# v1.net
KiCad netlist of a schematic drawn in Altium Designer
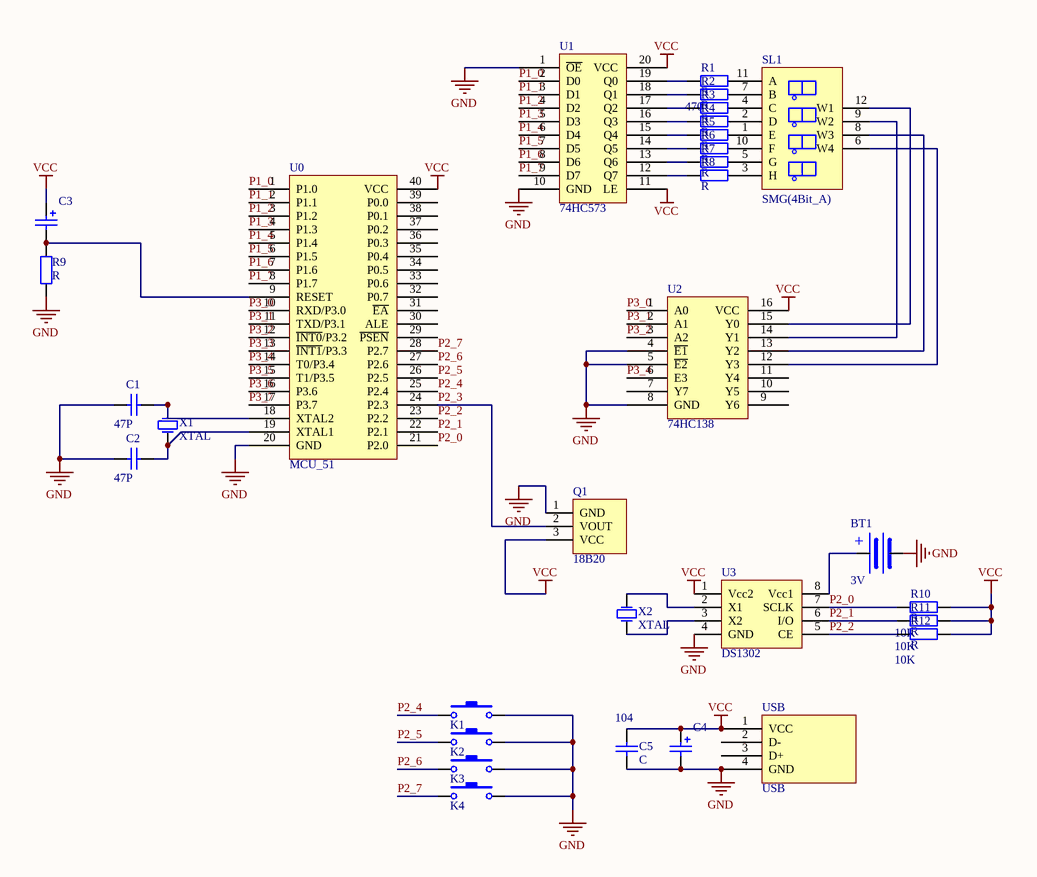
[diagram p0: 电子钟v1.SchDoc]

(export (version "E")
  (design (tool "Eeschema 10.0.6"))
  (components
    (comp (ref "BT1") (value "3V") (footprint "DCH_22") (libsource (lib "我的库") (part "BATTER")))
    (comp (ref "C1")
      (value "47pf")
      (footprint "瓷片电容")
      (fields (field (name "SIZE") "47P"))
      (libsource (lib "我的库") (part "C"))
    )
    (comp (ref "C2")
      (value "C")
      (footprint "瓷片电容")
      (fields (field (name "SIZE") "47P"))
      (libsource (lib "我的库") (part "C"))
    )
    (comp (ref "C3") (value "CD") (footprint "电解电容（小型）") (libsource (lib "我的库") (part "CD")))
    (comp (ref "C4") (value "CD") (footprint "电解电容（小型）") (libsource (lib "我的库") (part "CD")))
    (comp (ref "C5")
      (value "C")
      (footprint "瓷片电容")
      (fields (field (name "SIZE") "104"))
      (libsource (lib "我的库") (part "C"))
    )
    (comp (ref "K1")
      (value "switch-anniu")
      (footprint "6*6按钮开关")
      (libsource (lib "我的库") (part "switch-anniu"))
    )
    (comp (ref "K2")
      (value "switch-anniu")
      (footprint "6*6按钮开关")
      (libsource (lib "我的库") (part "switch-anniu"))
    )
    (comp (ref "K3")
      (value "switch-anniu")
      (footprint "6*6按钮开关")
      (libsource (lib "我的库") (part "switch-anniu"))
    )
    (comp (ref "K4")
      (value "switch-anniu")
      (footprint "6*6按钮开关")
      (libsource (lib "我的库") (part "switch-anniu"))
    )
    (comp (ref "Q1") (value "18B20") (footprint "三极管（小体3个脚）") (libsource (lib "我的库") (part "18B20")))
    (comp (ref "R1")
      (value "R")
      (footprint "电阻-0.25W")
      (fields (field (name "SIZE") "470"))
      (libsource (lib "我的库") (part "R"))
    )
    (comp (ref "R2") (value "R") (footprint "电阻-0.25W") (libsource (lib "我的库") (part "R")))
    (comp (ref "R3") (value "R") (footprint "电阻-0.25W") (libsource (lib "我的库") (part "R")))
    (comp (ref "R4") (value "R") (footprint "电阻-0.25W") (libsource (lib "我的库") (part "R")))
    (comp (ref "R5") (value "R") (footprint "电阻-0.25W") (libsource (lib "我的库") (part "R")))
    (comp (ref "R6") (value "R") (footprint "电阻-0.25W") (libsource (lib "我的库") (part "R")))
    (comp (ref "R7") (value "R") (footprint "电阻-0.25W") (libsource (lib "我的库") (part "R")))
    (comp (ref "R8") (value "R") (footprint "电阻-0.25W") (libsource (lib "我的库") (part "R")))
    (comp (ref "R9") (value "R") (footprint "电阻-0.25W") (libsource (lib "") (part "R_1")))
    (comp (ref "R10")
      (value "R")
      (footprint "电阻-0.25W")
      (fields (field (name "SIZE") "10K"))
      (libsource (lib "我的库") (part "R"))
    )
    (comp (ref "R11")
      (value "R")
      (footprint "电阻-0.25W")
      (fields (field (name "SIZE") "10K"))
      (libsource (lib "我的库") (part "R"))
    )
    (comp (ref "R12")
      (value "R")
      (footprint "电阻-0.25W")
      (fields (field (name "SIZE") "10K"))
      (libsource (lib "我的库") (part "R"))
    )
    (comp (ref "SL1")
      (value "SMG(4Bit_A)")
      (footprint "4位数码管（19*50mm）")
      (libsource (lib "我的库") (part "SMG(4Bit_A)"))
    )
    (comp (ref "U0") (value "MCU_51") (footprint "DIP-40") (libsource (lib "我的库") (part "MCU_51")))
    (comp (ref "U1") (value "74HC573") (footprint "DIP20插座") (libsource (lib "mylib") (part "74HC573")))
    (comp (ref "U2") (value "74HC138") (footprint "DIP16插座") (libsource (lib "mylib") (part "74HC138")))
    (comp (ref "U3") (value "DS1302") (footprint "DIP-8") (libsource (lib "我的库") (part "DS1302")))
    (comp (ref "USB") (value "USB") (footprint "USB阴头") (libsource (lib "GBY的原理图库") (part "USB")))
    (comp (ref "X1") (value "XTAL") (footprint "无源晶体（2个脚）") (libsource (lib "我的库") (part "XTAL")))
    (comp (ref "X2") (value "XTAL") (footprint "无源晶体（小）") (libsource (lib "我的库") (part "XTAL")))
  )
  (nets
    (net (code "1") (name "/P1_0") (class "Default")
      (node (ref "U0") (pin "1") (pinfunction "P1.0_1") (pintype "passive"))
      (node (ref "U1") (pin "2") (pinfunction "D0_2") (pintype "passive"))
    )
    (net (code "2") (name "/P1_1") (class "Default")
      (node (ref "U0") (pin "2") (pinfunction "P1.1_2") (pintype "passive"))
      (node (ref "U1") (pin "3") (pinfunction "D1_3") (pintype "passive"))
    )
    (net (code "3") (name "/P1_2") (class "Default")
      (node (ref "U0") (pin "3") (pinfunction "P1.2_3") (pintype "passive"))
      (node (ref "U1") (pin "4") (pinfunction "D2_4") (pintype "passive"))
    )
    (net (code "4") (name "/P1_3") (class "Default")
      (node (ref "U0") (pin "4") (pinfunction "P1.3_4") (pintype "passive"))
      (node (ref "U1") (pin "5") (pinfunction "D3_5") (pintype "passive"))
    )
    (net (code "5") (name "/P1_4") (class "Default")
      (node (ref "U0") (pin "5") (pinfunction "P1.4_5") (pintype "passive"))
      (node (ref "U1") (pin "6") (pinfunction "D4_6") (pintype "passive"))
    )
    (net (code "6") (name "/P1_5") (class "Default")
      (node (ref "U0") (pin "6") (pinfunction "P1.5_6") (pintype "passive"))
      (node (ref "U1") (pin "7") (pinfunction "D5_7") (pintype "passive"))
    )
    (net (code "7") (name "/P1_6") (class "Default")
      (node (ref "U0") (pin "7") (pinfunction "P1.6_7") (pintype "passive"))
      (node (ref "U1") (pin "8") (pinfunction "D6_8") (pintype "passive"))
    )
    (net (code "8") (name "/P1_7") (class "Default")
      (node (ref "U0") (pin "8") (pinfunction "P1.7_8") (pintype "passive"))
      (node (ref "U1") (pin "9") (pinfunction "D7_9") (pintype "passive"))
    )
    (net (code "9") (name "/P2_0") (class "Default")
      (node (ref "R10") (pin "1") (pinfunction "1_1") (pintype "passive"))
      (node (ref "U0") (pin "21") (pinfunction "P2.0_21") (pintype "passive"))
      (node (ref "U3") (pin "7") (pinfunction "SCLK_7") (pintype "passive"))
    )
    (net (code "10") (name "/P2_1") (class "Default")
      (node (ref "R11") (pin "1") (pinfunction "1_1") (pintype "passive"))
      (node (ref "U0") (pin "22") (pinfunction "P2.1_22") (pintype "passive"))
      (node (ref "U3") (pin "6") (pinfunction "I/O_6") (pintype "passive"))
    )
    (net (code "11") (name "/P2_2") (class "Default")
      (node (ref "R12") (pin "1") (pinfunction "1_1") (pintype "passive"))
      (node (ref "U0") (pin "23") (pinfunction "P2.2_23") (pintype "passive"))
      (node (ref "U3") (pin "5") (pinfunction "CE_5") (pintype "passive"))
    )
    (net (code "12") (name "/P2_3") (class "Default")
      (node (ref "Q1") (pin "2") (pinfunction "VOUT_2") (pintype "passive"))
      (node (ref "U0") (pin "24") (pinfunction "P2.3_24") (pintype "passive"))
    )
    (net (code "13") (name "/P2_4") (class "Default")
      (node (ref "K1") (pin "1") (pinfunction "1_1") (pintype "passive"))
      (node (ref "U0") (pin "25") (pinfunction "P2.4_25") (pintype "passive"))
    )
    (net (code "14") (name "/P2_5") (class "Default")
      (node (ref "K2") (pin "1") (pinfunction "1_1") (pintype "passive"))
      (node (ref "U0") (pin "26") (pinfunction "P2.5_26") (pintype "passive"))
    )
    (net (code "15") (name "/P2_6") (class "Default")
      (node (ref "K3") (pin "1") (pinfunction "1_1") (pintype "passive"))
      (node (ref "U0") (pin "27") (pinfunction "P2.6_27") (pintype "passive"))
    )
    (net (code "16") (name "/P2_7") (class "Default")
      (node (ref "K4") (pin "1") (pinfunction "1_1") (pintype "passive"))
      (node (ref "U0") (pin "28") (pinfunction "P2.7_28") (pintype "passive"))
    )
    (net (code "17") (name "/P3_0") (class "Default")
      (node (ref "U0") (pin "10") (pinfunction "RXD/P3.0_10") (pintype "passive"))
      (node (ref "U2") (pin "1") (pinfunction "A0_1") (pintype "passive"))
    )
    (net (code "18") (name "/P3_1") (class "Default")
      (node (ref "U0") (pin "11") (pinfunction "TXD/P3.1_11") (pintype "passive"))
      (node (ref "U2") (pin "2") (pinfunction "A1_2") (pintype "passive"))
    )
    (net (code "19") (name "/P3_2") (class "Default")
      (node (ref "U0") (pin "12") (pinfunction "~{INT0}/P3.2_12") (pintype "passive"))
      (node (ref "U2") (pin "3") (pinfunction "A2_3") (pintype "passive"))
    )
    (net (code "20") (name "/P3_3") (class "Default")
      (node (ref "U0") (pin "13") (pinfunction "~{INT1}/P3.3_13") (pintype "passive"))
    )
    (net (code "21") (name "/P3_4") (class "Default")
      (node (ref "U0") (pin "14") (pinfunction "T0/P3.4_14") (pintype "passive"))
      (node (ref "U2") (pin "6") (pinfunction "E3_6") (pintype "passive"))
    )
    (net (code "22") (name "/P3_5") (class "Default")
      (node (ref "U0") (pin "15") (pinfunction "T1/P3.5_15") (pintype "passive"))
    )
    (net (code "23") (name "/P3_6") (class "Default")
      (node (ref "U0") (pin "16") (pinfunction "P3.6_16") (pintype "passive"))
    )
    (net (code "24") (name "/P3_7") (class "Default")
      (node (ref "U0") (pin "17") (pinfunction "P3.7_17") (pintype "passive"))
    )
    (net (code "25") (name "GND") (class "Default")
      (node (ref "BT1") (pin "2") (pinfunction "GND_2") (pintype "passive"))
      (node (ref "C1") (pin "1") (pinfunction "1_1") (pintype "passive"))
      (node (ref "C2") (pin "1") (pinfunction "1_1") (pintype "passive"))
      (node (ref "C4") (pin "2") (pinfunction "2_2") (pintype "passive"))
      (node (ref "C5") (pin "1") (pinfunction "1_1") (pintype "passive"))
      (node (ref "K1") (pin "2") (pinfunction "2_2") (pintype "passive"))
      (node (ref "K2") (pin "2") (pinfunction "2_2") (pintype "passive"))
      (node (ref "K3") (pin "2") (pinfunction "2_2") (pintype "passive"))
      (node (ref "K4") (pin "2") (pinfunction "2_2") (pintype "passive"))
      (node (ref "Q1") (pin "1") (pinfunction "GND_1") (pintype "passive"))
      (node (ref "R9") (pin "1") (pinfunction "1_1") (pintype "passive"))
      (node (ref "U0") (pin "20") (pinfunction "GND_20") (pintype "passive"))
      (node (ref "U1") (pin "1") (pinfunction "~{OE}_1") (pintype "passive"))
      (node (ref "U1") (pin "10") (pinfunction "GND_10") (pintype "passive"))
      (node (ref "U2") (pin "4") (pinfunction "~{E1}_4") (pintype "passive"))
      (node (ref "U2") (pin "5") (pinfunction "~{E2}_5") (pintype "passive"))
      (node (ref "U2") (pin "8") (pinfunction "GND_8") (pintype "power_in"))
      (node (ref "U3") (pin "4") (pinfunction "GND_4") (pintype "passive"))
      (node (ref "USB") (pin "4") (pinfunction "GND_4") (pintype "passive"))
    )
    (net (code "26") (name "Net-(BT1-VCC)") (class "Default")
      (node (ref "BT1") (pin "1") (pinfunction "VCC_1") (pintype "passive"))
      (node (ref "U3") (pin "8") (pinfunction "Vcc1_8") (pintype "passive"))
    )
    (net (code "27") (name "Net-(SL1-A)") (class "Default")
      (node (ref "R1") (pin "2") (pinfunction "2_2") (pintype "passive"))
      (node (ref "SL1") (pin "11") (pinfunction "A_11") (pintype "passive"))
    )
    (net (code "28") (name "Net-(SL1-B)") (class "Default")
      (node (ref "R2") (pin "2") (pinfunction "2_2") (pintype "passive"))
      (node (ref "SL1") (pin "7") (pinfunction "B_7") (pintype "passive"))
    )
    (net (code "29") (name "Net-(SL1-C)") (class "Default")
      (node (ref "R3") (pin "2") (pinfunction "2_2") (pintype "passive"))
      (node (ref "SL1") (pin "4") (pinfunction "C_4") (pintype "passive"))
    )
    (net (code "30") (name "Net-(SL1-D)") (class "Default")
      (node (ref "R4") (pin "2") (pinfunction "2_2") (pintype "passive"))
      (node (ref "SL1") (pin "2") (pinfunction "D_2") (pintype "passive"))
    )
    (net (code "31") (name "Net-(SL1-E)") (class "Default")
      (node (ref "R5") (pin "2") (pinfunction "2_2") (pintype "passive"))
      (node (ref "SL1") (pin "1") (pinfunction "E_1") (pintype "passive"))
    )
    (net (code "32") (name "Net-(SL1-F)") (class "Default")
      (node (ref "R6") (pin "2") (pinfunction "2_2") (pintype "passive"))
      (node (ref "SL1") (pin "10") (pinfunction "F_10") (pintype "passive"))
    )
    (net (code "33") (name "Net-(SL1-G)") (class "Default")
      (node (ref "R7") (pin "2") (pinfunction "2_2") (pintype "passive"))
      (node (ref "SL1") (pin "5") (pinfunction "G_5") (pintype "passive"))
    )
    (net (code "34") (name "Net-(SL1-H)") (class "Default")
      (node (ref "R8") (pin "2") (pinfunction "2_2") (pintype "passive"))
      (node (ref "SL1") (pin "3") (pinfunction "H_3") (pintype "passive"))
    )
    (net (code "35") (name "Net-(SL1-W1)") (class "Default")
      (node (ref "SL1") (pin "12") (pinfunction "W1_12") (pintype "passive"))
      (node (ref "U2") (pin "15") (pinfunction "Y0_15") (pintype "passive"))
    )
    (net (code "36") (name "Net-(SL1-W2)") (class "Default")
      (node (ref "SL1") (pin "9") (pinfunction "W2_9") (pintype "passive"))
      (node (ref "U2") (pin "14") (pinfunction "Y1_14") (pintype "passive"))
    )
    (net (code "37") (name "Net-(SL1-W3)") (class "Default")
      (node (ref "SL1") (pin "8") (pinfunction "W3_8") (pintype "passive"))
      (node (ref "U2") (pin "13") (pinfunction "Y2_13") (pintype "passive"))
    )
    (net (code "38") (name "Net-(SL1-W4)") (class "Default")
      (node (ref "SL1") (pin "6") (pinfunction "W4_6") (pintype "passive"))
      (node (ref "U2") (pin "12") (pinfunction "Y3_12") (pintype "passive"))
    )
    (net (code "39") (name "Net-(U0-RESET)") (class "Default")
      (node (ref "C3") (pin "2") (pinfunction "2_2") (pintype "passive"))
      (node (ref "R9") (pin "2") (pinfunction "2_2") (pintype "passive"))
      (node (ref "U0") (pin "9") (pinfunction "RESET_9") (pintype "passive"))
    )
    (net (code "40") (name "Net-(U0-XTAL1)") (class "Default")
      (node (ref "C2") (pin "2") (pinfunction "2_2") (pintype "passive"))
      (node (ref "U0") (pin "19") (pinfunction "XTAL1_19") (pintype "passive"))
      (node (ref "X1") (pin "1") (pinfunction "OSC1_1") (pintype "passive"))
    )
    (net (code "41") (name "Net-(U0-XTAL2)") (class "Default")
      (node (ref "C1") (pin "2") (pinfunction "2_2") (pintype "passive"))
      (node (ref "U0") (pin "18") (pinfunction "XTAL2_18") (pintype "passive"))
      (node (ref "X1") (pin "2") (pinfunction "OSC2_2") (pintype "passive"))
    )
    (net (code "42") (name "Net-(U1-Q0)") (class "Default")
      (node (ref "R1") (pin "1") (pinfunction "1_1") (pintype "passive"))
      (node (ref "U1") (pin "19") (pinfunction "Q0_19") (pintype "passive"))
    )
    (net (code "43") (name "Net-(U1-Q1)") (class "Default")
      (node (ref "R2") (pin "1") (pinfunction "1_1") (pintype "passive"))
      (node (ref "U1") (pin "18") (pinfunction "Q1_18") (pintype "passive"))
    )
    (net (code "44") (name "Net-(U1-Q2)") (class "Default")
      (node (ref "R3") (pin "1") (pinfunction "1_1") (pintype "passive"))
      (node (ref "U1") (pin "17") (pinfunction "Q2_17") (pintype "passive"))
    )
    (net (code "45") (name "Net-(U1-Q3)") (class "Default")
      (node (ref "R4") (pin "1") (pinfunction "1_1") (pintype "passive"))
      (node (ref "U1") (pin "16") (pinfunction "Q3_16") (pintype "passive"))
    )
    (net (code "46") (name "Net-(U1-Q4)") (class "Default")
      (node (ref "R5") (pin "1") (pinfunction "1_1") (pintype "passive"))
      (node (ref "U1") (pin "15") (pinfunction "Q4_15") (pintype "passive"))
    )
    (net (code "47") (name "Net-(U1-Q5)") (class "Default")
      (node (ref "R6") (pin "1") (pinfunction "1_1") (pintype "passive"))
      (node (ref "U1") (pin "14") (pinfunction "Q5_14") (pintype "passive"))
    )
    (net (code "48") (name "Net-(U1-Q6)") (class "Default")
      (node (ref "R7") (pin "1") (pinfunction "1_1") (pintype "passive"))
      (node (ref "U1") (pin "13") (pinfunction "Q6_13") (pintype "passive"))
    )
    (net (code "49") (name "Net-(U1-Q7)") (class "Default")
      (node (ref "R8") (pin "1") (pinfunction "1_1") (pintype "passive"))
      (node (ref "U1") (pin "12") (pinfunction "Q7_12") (pintype "passive"))
    )
    (net (code "50") (name "Net-(U3-X1)") (class "Default")
      (node (ref "U3") (pin "2") (pinfunction "X1_2") (pintype "passive"))
      (node (ref "X2") (pin "2") (pinfunction "OSC2_2") (pintype "passive"))
    )
    (net (code "51") (name "Net-(U3-X2)") (class "Default")
      (node (ref "U3") (pin "3") (pinfunction "X2_3") (pintype "passive"))
      (node (ref "X2") (pin "1") (pinfunction "OSC1_1") (pintype "passive"))
    )
    (net (code "52") (name "VCC") (class "Default")
      (node (ref "C3") (pin "1") (pinfunction "1_1") (pintype "passive"))
      (node (ref "C4") (pin "1") (pinfunction "1_1") (pintype "passive"))
      (node (ref "C5") (pin "2") (pinfunction "2_2") (pintype "passive"))
      (node (ref "Q1") (pin "3") (pinfunction "VCC_3") (pintype "passive"))
      (node (ref "R10") (pin "2") (pinfunction "2_2") (pintype "passive"))
      (node (ref "R11") (pin "2") (pinfunction "2_2") (pintype "passive"))
      (node (ref "R12") (pin "2") (pinfunction "2_2") (pintype "passive"))
      (node (ref "U0") (pin "40") (pinfunction "VCC_40") (pintype "passive"))
      (node (ref "U1") (pin "11") (pinfunction "LE_11") (pintype "passive"))
      (node (ref "U1") (pin "20") (pinfunction "VCC_20") (pintype "passive"))
      (node (ref "U2") (pin "16") (pinfunction "VCC_16") (pintype "power_in"))
      (node (ref "U3") (pin "1") (pinfunction "Vcc2_1") (pintype "passive"))
      (node (ref "USB") (pin "1") (pinfunction "VCC_1") (pintype "passive"))
    )
    (net (code "53") (name "unconnected-(U0-ALE-Pad30)") (class "Default")
      (node (ref "U0") (pin "30") (pinfunction "ALE_30") (pintype "passive"))
    )
    (net (code "54") (name "unconnected-(U0-P0.0-Pad39)") (class "Default")
      (node (ref "U0") (pin "39") (pinfunction "P0.0_39") (pintype "passive"))
    )
    (net (code "55") (name "unconnected-(U0-P0.1-Pad38)") (class "Default")
      (node (ref "U0") (pin "38") (pinfunction "P0.1_38") (pintype "passive"))
    )
    (net (code "56") (name "unconnected-(U0-P0.2-Pad37)") (class "Default")
      (node (ref "U0") (pin "37") (pinfunction "P0.2_37") (pintype "passive"))
    )
    (net (code "57") (name "unconnected-(U0-P0.3-Pad36)") (class "Default")
      (node (ref "U0") (pin "36") (pinfunction "P0.3_36") (pintype "passive"))
    )
    (net (code "58") (name "unconnected-(U0-P0.4-Pad35)") (class "Default")
      (node (ref "U0") (pin "35") (pinfunction "P0.4_35") (pintype "passive"))
    )
    (net (code "59") (name "unconnected-(U0-P0.5-Pad34)") (class "Default")
      (node (ref "U0") (pin "34") (pinfunction "P0.5_34") (pintype "passive"))
    )
    (net (code "60") (name "unconnected-(U0-P0.6-Pad33)") (class "Default")
      (node (ref "U0") (pin "33") (pinfunction "P0.6_33") (pintype "passive"))
    )
    (net (code "61") (name "unconnected-(U0-P0.7-Pad32)") (class "Default")
      (node (ref "U0") (pin "32") (pinfunction "P0.7_32") (pintype "passive"))
    )
    (net (code "62") (name "unconnected-(U0-~{EA}-Pad31)") (class "Default")
      (node (ref "U0") (pin "31") (pinfunction "~{EA}_31") (pintype "passive"))
    )
    (net (code "63") (name "unconnected-(U0-~{PSEN}-Pad29)") (class "Default")
      (node (ref "U0") (pin "29") (pinfunction "~{PSEN}_29") (pintype "passive"))
    )
    (net (code "64") (name "unconnected-(U2-Y4-Pad11)") (class "Default")
      (node (ref "U2") (pin "11") (pinfunction "Y4_11") (pintype "passive"))
    )
    (net (code "65") (name "unconnected-(U2-Y5-Pad10)") (class "Default")
      (node (ref "U2") (pin "10") (pinfunction "Y5_10") (pintype "passive"))
    )
    (net (code "66") (name "unconnected-(U2-Y6-Pad9)") (class "Default")
      (node (ref "U2") (pin "9") (pinfunction "Y6_9") (pintype "passive"))
    )
    (net (code "67") (name "unconnected-(U2-Y7-Pad7)") (class "Default")
      (node (ref "U2") (pin "7") (pinfunction "Y7_7") (pintype "passive"))
    )
    (net (code "68") (name "unconnected-(USB-D+-Pad3)") (class "Default")
      (node (ref "USB") (pin "3") (pinfunction "D+_3") (pintype "passive"))
    )
    (net (code "69") (name "unconnected-(USB-D--Pad2)") (class "Default")
      (node (ref "USB") (pin "2") (pinfunction "D-_2") (pintype "passive"))
    )
  )
)
